# MINI_SAM_D51_014.net
KiCad netlist of a schematic drawn in EAGLE
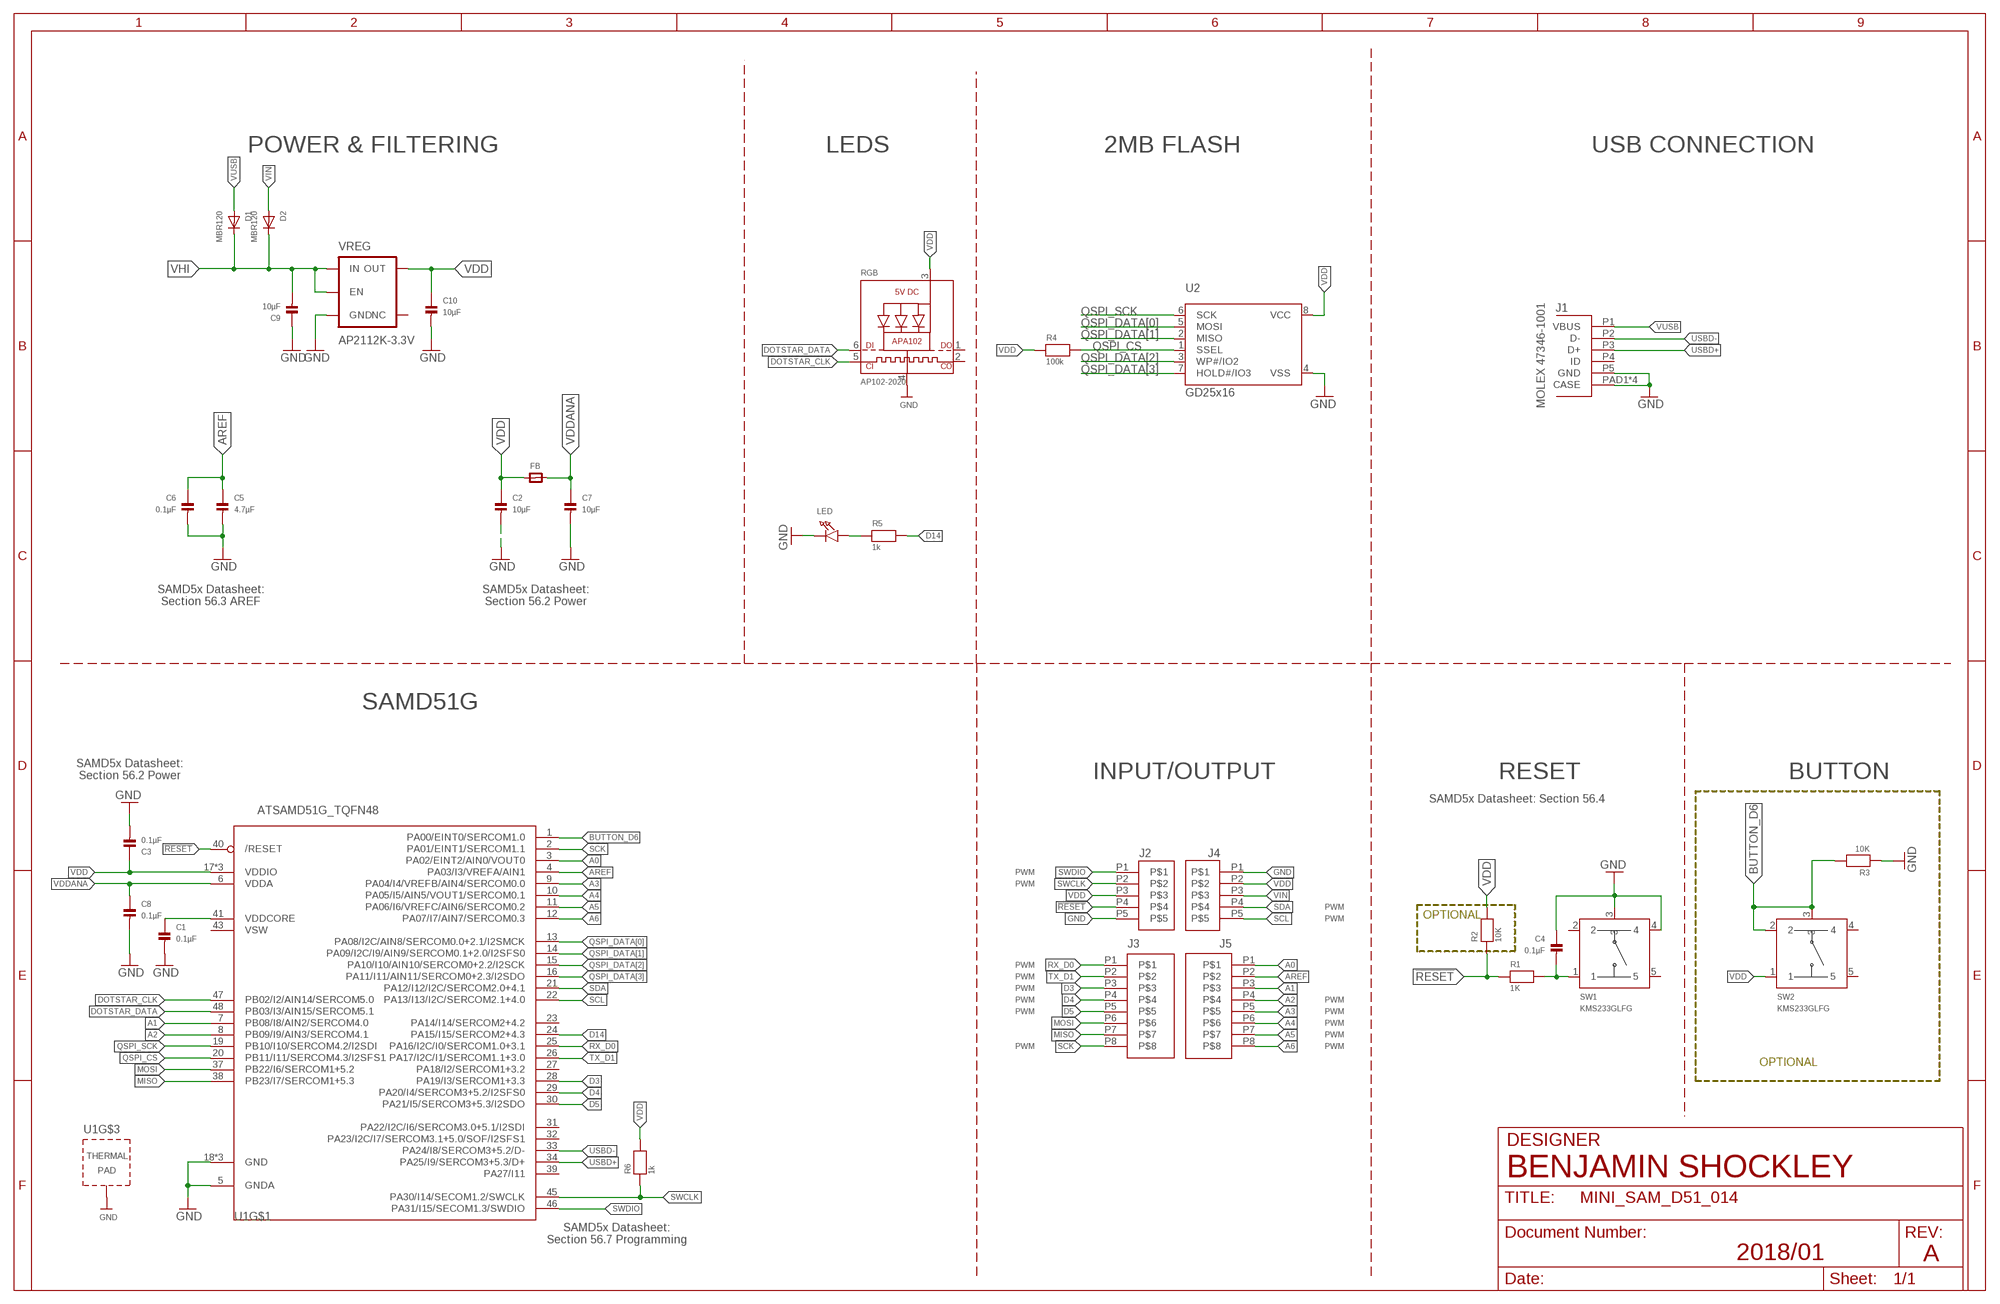
[diagram p0: schematic, sheet 1]

(export (version "E")
  (design (tool "Eeschema 10.0.6"))
  (components
    (comp (ref "C1")
      (value "0.1µF")
      (footprint "eagle-import:_0603MP")
      (libsource (lib "eagle-import") (part "CAP_CERAMIC_0603MP"))
    )
    (comp (ref "C2")
      (value "10µF")
      (footprint "eagle-import:_0603MP")
      (libsource (lib "eagle-import") (part "CAP_CERAMIC_0603MP"))
    )
    (comp (ref "C3")
      (value "0.1µF")
      (footprint "eagle-import:_0603MP")
      (libsource (lib "eagle-import") (part "CAP_CERAMIC_0603MP"))
    )
    (comp (ref "C4")
      (value "0.1µF")
      (footprint "eagle-import:_0603MP")
      (libsource (lib "eagle-import") (part "CAP_CERAMIC_0603MP"))
    )
    (comp (ref "C5")
      (value "4.7µF")
      (footprint "eagle-import:_0603MP")
      (libsource (lib "eagle-import") (part "CAP_CERAMIC_0603MP"))
    )
    (comp (ref "C6")
      (value "0.1µF")
      (footprint "eagle-import:_0603MP")
      (libsource (lib "eagle-import") (part "CAP_CERAMIC_0603MP"))
    )
    (comp (ref "C7")
      (value "10µF")
      (footprint "eagle-import:_0603MP")
      (libsource (lib "eagle-import") (part "CAP_CERAMIC_0603MP"))
    )
    (comp (ref "C8")
      (value "0.1µF")
      (footprint "eagle-import:_0603MP")
      (libsource (lib "eagle-import") (part "CAP_CERAMIC_0603MP"))
    )
    (comp (ref "C9")
      (value "10µF")
      (footprint "eagle-import:_0603MP")
      (libsource (lib "eagle-import") (part "CAP_CERAMIC_0603MP"))
    )
    (comp (ref "C10")
      (value "10µF")
      (footprint "eagle-import:_0603MP")
      (libsource (lib "eagle-import") (part "CAP_CERAMIC_0603MP"))
    )
    (comp (ref "D1")
      (value "MBR120")
      (footprint "eagle-import:SOD-123FL")
      (libsource (lib "eagle-import") (part "DIODE_SOD-123FL"))
    )
    (comp (ref "D2")
      (value "MBR120")
      (footprint "eagle-import:SOD-123FL")
      (libsource (lib "eagle-import") (part "DIODE_SOD-123FL"))
    )
    (comp (ref "FB")
      (value "FERRITE_0603MP")
      (footprint "eagle-import:_0603MP")
      (libsource (lib "eagle-import") (part "FERRITE_0603MP"))
    )
    (comp (ref "J1")
      (value "MOLEX_47346-100147346")
      (footprint "eagle-import:MOLEX_47346-1001")
      (libsource (lib "eagle-import") (part "MOLEX_47346-100147346"))
    )
    (comp (ref "J2")
      (value "1X5_HEADER_1.27MMCAST")
      (footprint "eagle-import:1X5_HEADER_1.27MM_CASTELLATED")
      (libsource (lib "eagle-import") (part "1X5_HEADER_1.27MMCAST"))
    )
    (comp (ref "J3")
      (value "1X8_HEADER_1.27MMCAST")
      (footprint "eagle-import:1X8_HEADER_1.27MM_CASTELLATED")
      (libsource (lib "eagle-import") (part "1X8_HEADER_1.27MMCAST"))
    )
    (comp (ref "J4")
      (value "1X5_HEADER_1.27MMCAST")
      (footprint "eagle-import:1X5_HEADER_1.27MM_CASTELLATED")
      (libsource (lib "eagle-import") (part "1X5_HEADER_1.27MMCAST"))
    )
    (comp (ref "J5")
      (value "1X8_HEADER_1.27MMCAST")
      (footprint "eagle-import:1X8_HEADER_1.27MM_CASTELLATED")
      (libsource (lib "eagle-import") (part "1X8_HEADER_1.27MMCAST"))
    )
    (comp (ref "LED")
      (value "LED0805_NOOUTLINE")
      (footprint "eagle-import:CHIPLED_0805_NOOUTLINE")
      (libsource (lib "eagle-import") (part "LED0805_NOOUTLINE"))
    )
    (comp (ref "R1")
      (value "1K")
      (footprint "eagle-import:_0603MP")
      (libsource (lib "eagle-import") (part "RESISTOR_0603MP"))
    )
    (comp (ref "R2")
      (value "10K")
      (footprint "eagle-import:_0603MP")
      (libsource (lib "eagle-import") (part "RESISTOR_0603MP"))
    )
    (comp (ref "R3")
      (value "10K")
      (footprint "eagle-import:_0603MP")
      (libsource (lib "eagle-import") (part "RESISTOR_0603MP"))
    )
    (comp (ref "R4")
      (value "100k")
      (footprint "eagle-import:_0603MP")
      (libsource (lib "eagle-import") (part "RESISTOR_0603MP"))
    )
    (comp (ref "R5")
      (value "1k")
      (footprint "eagle-import:_0603MP")
      (libsource (lib "eagle-import") (part "RESISTOR_0603MP"))
    )
    (comp (ref "R6")
      (value "1k")
      (footprint "eagle-import:_0603MP")
      (libsource (lib "eagle-import") (part "RESISTOR_0603MP"))
    )
    (comp (ref "RGB")
      (value "AP102-2020")
      (footprint "eagle-import:APA102_2020")
      (libsource (lib "eagle-import") (part "APA1022020"))
    )
    (comp (ref "SW1")
      (value "KMS233GLFG")
      (footprint "eagle-import:KMS_SWITCH")
      (libsource (lib "eagle-import") (part "KMS_SWITCHKMS"))
    )
    (comp (ref "SW2")
      (value "KMS233GLFG")
      (footprint "eagle-import:KMS_SWITCH")
      (libsource (lib "eagle-import") (part "KMS_SWITCHKMS"))
    )
    (comp (ref "U1")
      (value "ATSAMD51G_TQFN48")
      (footprint "eagle-import:TQFN48_7MM")
      (libsource (lib "eagle-import") (part "ATSAMD51G_TQFN48"))
    )
    (comp (ref "U2")
      (value "GD25x16")
      (footprint "eagle-import:USON8")
      (libsource (lib "eagle-import") (part "SPIFLASH_8PINUX"))
    )
    (comp (ref "VREG")
      (value "AP2112K-3.3V")
      (footprint "eagle-import:SOT23-5")
      (libsource (lib "eagle-import") (part "V_REG_AP2112K-3.3V"))
    )
  )
  (nets
    (net (code "1") (name "/VSW") (class "Default")
      (node (ref "U1") (pin "43") (pinfunction "VSW_43") (pintype "power_in"))
    )
    (net (code "2") (name "/~{RESET}") (class "Default")
      (node (ref "J2") (pin "P4") (pinfunction "P$4_P4") (pintype "bidirectional"))
      (node (ref "R1") (pin "1") (pinfunction "1_1") (pintype "passive"))
      (node (ref "R2") (pin "1") (pinfunction "1_1") (pintype "passive"))
      (node (ref "U1") (pin "40") (pinfunction "/RESET_40") (pintype "bidirectional"))
    )
    (net (code "3") (name "A0") (class "Default")
      (node (ref "J5") (pin "P1") (pinfunction "P$1_P1") (pintype "bidirectional"))
      (node (ref "U1") (pin "3") (pinfunction "PA02/EINT2/AIN0/VOUT0_3") (pintype "bidirectional"))
    )
    (net (code "4") (name "A1") (class "Default")
      (node (ref "J5") (pin "P3") (pinfunction "P$3_P3") (pintype "bidirectional"))
      (node (ref "U1") (pin "7") (pinfunction "PB08/I8/AIN2/SERCOM4.0_7") (pintype "bidirectional"))
    )
    (net (code "5") (name "A2") (class "Default")
      (node (ref "J5") (pin "P4") (pinfunction "P$4_P4") (pintype "bidirectional"))
      (node (ref "U1") (pin "8") (pinfunction "PB09/I9/AIN3/SERCOM4.1_8") (pintype "bidirectional"))
    )
    (net (code "6") (name "A3") (class "Default")
      (node (ref "J5") (pin "P5") (pinfunction "P$5_P5") (pintype "bidirectional"))
      (node (ref "U1") (pin "9") (pinfunction "PA04/I4/VREFB/AIN4/SERCOM0.0_9") (pintype "bidirectional"))
    )
    (net (code "7") (name "A4") (class "Default")
      (node (ref "J5") (pin "P6") (pinfunction "P$6_P6") (pintype "bidirectional"))
      (node (ref "U1") (pin "10") (pinfunction "PA05/I5/AIN5/VOUT1/SERCOM0.1_10") (pintype "bidirectional"))
    )
    (net (code "8") (name "A5") (class "Default")
      (node (ref "J5") (pin "P7") (pinfunction "P$7_P7") (pintype "bidirectional"))
      (node (ref "U1") (pin "11") (pinfunction "PA06/I6/VREFC/AIN6/SERCOM0.2_11") (pintype "bidirectional"))
    )
    (net (code "9") (name "A6") (class "Default")
      (node (ref "J5") (pin "P8") (pinfunction "P$8_P8") (pintype "bidirectional"))
      (node (ref "U1") (pin "12") (pinfunction "PA07/I7/AIN7/SERCOM0.3_12") (pintype "bidirectional"))
    )
    (net (code "10") (name "AREF") (class "Default")
      (node (ref "C5") (pin "1") (pinfunction "P$1_1") (pintype "passive"))
      (node (ref "C6") (pin "1") (pinfunction "P$1_1") (pintype "passive"))
      (node (ref "J5") (pin "P2") (pinfunction "P$2_P2") (pintype "bidirectional"))
      (node (ref "U1") (pin "4") (pinfunction "PA03/I3/VREFA/AIN1_4") (pintype "bidirectional"))
    )
    (net (code "11") (name "BUTTON_D6") (class "Default")
      (node (ref "R3") (pin "2") (pinfunction "2_2") (pintype "passive"))
      (node (ref "SW2") (pin "2") (pinfunction "2_2") (pintype "bidirectional"))
      (node (ref "SW2") (pin "3") (pinfunction "3_3") (pintype "bidirectional"))
      (node (ref "U1") (pin "1") (pinfunction "PA00/EINT0/SERCOM1.0_1") (pintype "bidirectional"))
    )
    (net (code "12") (name "D3") (class "Default")
      (node (ref "J3") (pin "P3") (pinfunction "P$3_P3") (pintype "bidirectional"))
      (node (ref "U1") (pin "28") (pinfunction "PA19/I3/SERCOM1+3.3_28") (pintype "bidirectional"))
    )
    (net (code "13") (name "D4") (class "Default")
      (node (ref "J3") (pin "P4") (pinfunction "P$4_P4") (pintype "bidirectional"))
      (node (ref "U1") (pin "29") (pinfunction "PA20/I4/SERCOM3+5.2/I2SFS0_29") (pintype "bidirectional"))
    )
    (net (code "14") (name "D5") (class "Default")
      (node (ref "J3") (pin "P5") (pinfunction "P$5_P5") (pintype "bidirectional"))
      (node (ref "U1") (pin "30") (pinfunction "PA21/I5/SERCOM3+5.3/I2SDO_30") (pintype "bidirectional"))
    )
    (net (code "15") (name "D14") (class "Default")
      (node (ref "R5") (pin "2") (pinfunction "2_2") (pintype "passive"))
      (node (ref "U1") (pin "24") (pinfunction "PA15/I15/SERCOM2+4.3_24") (pintype "bidirectional"))
    )
    (net (code "16") (name "DOTSTAR_CLK") (class "Default")
      (node (ref "RGB") (pin "5") (pinfunction "CKI_5") (pintype "input"))
      (node (ref "U1") (pin "47") (pinfunction "PB02/I2/AIN14/SERCOM5.0_47") (pintype "bidirectional"))
    )
    (net (code "17") (name "DOTSTAR_DATA") (class "Default")
      (node (ref "RGB") (pin "6") (pinfunction "DI_6") (pintype "input"))
      (node (ref "U1") (pin "48") (pinfunction "PB03/I3/AIN15/SERCOM5.1_48") (pintype "bidirectional"))
    )
    (net (code "18") (name "GND") (class "Default")
      (node (ref "C1") (pin "2") (pinfunction "P$2_2") (pintype "passive"))
      (node (ref "C10") (pin "2") (pinfunction "P$2_2") (pintype "passive"))
      (node (ref "C2") (pin "2") (pinfunction "P$2_2") (pintype "passive"))
      (node (ref "C3") (pin "2") (pinfunction "P$2_2") (pintype "passive"))
      (node (ref "C4") (pin "1") (pinfunction "P$1_1") (pintype "passive"))
      (node (ref "C5") (pin "2") (pinfunction "P$2_2") (pintype "passive"))
      (node (ref "C6") (pin "2") (pinfunction "P$2_2") (pintype "passive"))
      (node (ref "C7") (pin "2") (pinfunction "P$2_2") (pintype "passive"))
      (node (ref "C8") (pin "2") (pinfunction "P$2_2") (pintype "passive"))
      (node (ref "C9") (pin "1") (pinfunction "P$1_1") (pintype "passive"))
      (node (ref "J1") (pin "P5") (pinfunction "GND_P5") (pintype "power_in"))
      (node (ref "J1") (pin "PAD1") (pinfunction "CASE_PAD1") (pintype "bidirectional"))
      (node (ref "J1") (pin "PAD2") (pinfunction "CASE_PAD2") (pintype "bidirectional"))
      (node (ref "J1") (pin "PAD3") (pinfunction "CASE_PAD3") (pintype "bidirectional"))
      (node (ref "J1") (pin "PAD4") (pinfunction "CASE_PAD4") (pintype "bidirectional"))
      (node (ref "J2") (pin "P5") (pinfunction "P$5_P5") (pintype "bidirectional"))
      (node (ref "J4") (pin "P1") (pinfunction "P$1_P1") (pintype "bidirectional"))
      (node (ref "LED") (pin "C") (pinfunction "C_C") (pintype "passive"))
      (node (ref "R3") (pin "1") (pinfunction "1_1") (pintype "passive"))
      (node (ref "RGB") (pin "4") (pinfunction "GND_4") (pintype "power_in"))
      (node (ref "SW1") (pin "3") (pinfunction "3_3") (pintype "bidirectional"))
      (node (ref "SW1") (pin "4") (pinfunction "4_4") (pintype "bidirectional"))
      (node (ref "U1") (pin "18") (pinfunction "GND_18") (pintype "power_in"))
      (node (ref "U1") (pin "35") (pinfunction "GND_35") (pintype "power_in"))
      (node (ref "U1") (pin "42") (pinfunction "GND_42") (pintype "power_in"))
      (node (ref "U1") (pin "5") (pinfunction "GNDA_5") (pintype "power_in"))
      (node (ref "U1") (pin "THERMAL") (pinfunction "TP_THERMAL") (pintype "power_in"))
      (node (ref "U2") (pin "4") (pinfunction "VSS_4") (pintype "bidirectional"))
      (node (ref "VREG") (pin "2") (pinfunction "GND_2") (pintype "input"))
    )
    (net (code "19") (name "MISO") (class "Default")
      (node (ref "J3") (pin "P7") (pinfunction "P$7_P7") (pintype "bidirectional"))
      (node (ref "U1") (pin "38") (pinfunction "PB23/I7/SERCOM1+5.3_38") (pintype "bidirectional"))
    )
    (net (code "20") (name "MOSI") (class "Default")
      (node (ref "J3") (pin "P6") (pinfunction "P$6_P6") (pintype "bidirectional"))
      (node (ref "U1") (pin "37") (pinfunction "PB22/I6/SERCOM1+5.2_37") (pintype "bidirectional"))
    )
    (net (code "21") (name "Net-(C1-P$1)") (class "Default")
      (node (ref "C1") (pin "1") (pinfunction "P$1_1") (pintype "passive"))
      (node (ref "U1") (pin "41") (pinfunction "VDDCORE_41") (pintype "power_in"))
    )
    (net (code "22") (name "Net-(C4-P$2)") (class "Default")
      (node (ref "C4") (pin "2") (pinfunction "P$2_2") (pintype "passive"))
      (node (ref "R1") (pin "2") (pinfunction "2_2") (pintype "passive"))
      (node (ref "SW1") (pin "1") (pinfunction "1_1") (pintype "bidirectional"))
    )
    (net (code "23") (name "Net-(LED-PadA)") (class "Default")
      (node (ref "LED") (pin "A") (pinfunction "A_A") (pintype "passive"))
      (node (ref "R5") (pin "1") (pinfunction "1_1") (pintype "passive"))
    )
    (net (code "24") (name "QSPI_CS") (class "Default")
      (node (ref "R4") (pin "2") (pinfunction "2_2") (pintype "passive"))
      (node (ref "U1") (pin "20") (pinfunction "PB11/I11/SERCOM4.3/I2SFS1_20") (pintype "bidirectional"))
      (node (ref "U2") (pin "1") (pinfunction "SSEL_1") (pintype "bidirectional"))
    )
    (net (code "25") (name "QSPI_DATA[0]") (class "Default")
      (node (ref "U1") (pin "13") (pinfunction "PA08/I2C/AIN8/SERCOM0.0+2.1/I2SMCK_13") (pintype "bidirectional"))
      (node (ref "U2") (pin "5") (pinfunction "MOSI_5") (pintype "bidirectional"))
    )
    (net (code "26") (name "QSPI_DATA[1]") (class "Default")
      (node (ref "U1") (pin "14") (pinfunction "PA09/I2C/I9/AIN9/SERCOM0.1+2.0/I2SFS0_14") (pintype "bidirectional"))
      (node (ref "U2") (pin "2") (pinfunction "MISO_2") (pintype "bidirectional"))
    )
    (net (code "27") (name "QSPI_DATA[2]") (class "Default")
      (node (ref "U1") (pin "15") (pinfunction "PA10/I10/AIN10/SERCOM0+2.2/I2SCK_15") (pintype "bidirectional"))
      (node (ref "U2") (pin "3") (pinfunction "WP#/IO2_3") (pintype "bidirectional"))
    )
    (net (code "28") (name "QSPI_DATA[3]") (class "Default")
      (node (ref "U1") (pin "16") (pinfunction "PA11/I11/AIN11/SERCOM0+2.3/I2SDO_16") (pintype "bidirectional"))
      (node (ref "U2") (pin "7") (pinfunction "HOLD#/IO3_7") (pintype "bidirectional"))
    )
    (net (code "29") (name "QSPI_SCK") (class "Default")
      (node (ref "U1") (pin "19") (pinfunction "PB10/I10/SERCOM4.2/I2SDI_19") (pintype "bidirectional"))
      (node (ref "U2") (pin "6") (pinfunction "SCK_6") (pintype "bidirectional"))
    )
    (net (code "30") (name "RX_D0") (class "Default")
      (node (ref "J3") (pin "P1") (pinfunction "P$1_P1") (pintype "bidirectional"))
      (node (ref "U1") (pin "25") (pinfunction "PA16/I2C/I0/SERCOM1.0+3.1_25") (pintype "bidirectional"))
    )
    (net (code "31") (name "SCK") (class "Default")
      (node (ref "J3") (pin "P8") (pinfunction "P$8_P8") (pintype "bidirectional"))
      (node (ref "U1") (pin "2") (pinfunction "PA01/EINT1/SERCOM1.1_2") (pintype "bidirectional"))
    )
    (net (code "32") (name "SCL") (class "Default")
      (node (ref "J4") (pin "P5") (pinfunction "P$5_P5") (pintype "bidirectional"))
      (node (ref "U1") (pin "22") (pinfunction "PA13/I13/I2C/SERCOM2.1+4.0_22") (pintype "bidirectional"))
    )
    (net (code "33") (name "SDA") (class "Default")
      (node (ref "J4") (pin "P4") (pinfunction "P$4_P4") (pintype "bidirectional"))
      (node (ref "U1") (pin "21") (pinfunction "PA12/I12/I2C/SERCOM2.0+4.1_21") (pintype "bidirectional"))
    )
    (net (code "34") (name "SWCLK") (class "Default")
      (node (ref "J2") (pin "P2") (pinfunction "P$2_P2") (pintype "bidirectional"))
      (node (ref "R6") (pin "1") (pinfunction "1_1") (pintype "passive"))
      (node (ref "U1") (pin "45") (pinfunction "PA30/I14/SECOM1.2/SWCLK_45") (pintype "bidirectional"))
    )
    (net (code "35") (name "SWDIO") (class "Default")
      (node (ref "J2") (pin "P1") (pinfunction "P$1_P1") (pintype "bidirectional"))
      (node (ref "U1") (pin "46") (pinfunction "PA31/I15/SECOM1.3/SWDIO_46") (pintype "bidirectional"))
    )
    (net (code "36") (name "TX_D1") (class "Default")
      (node (ref "J3") (pin "P2") (pinfunction "P$2_P2") (pintype "bidirectional"))
      (node (ref "U1") (pin "26") (pinfunction "PA17/I2C/I1/SERCOM1.1+3.0_26") (pintype "bidirectional"))
    )
    (net (code "37") (name "USBD+") (class "Default")
      (node (ref "J1") (pin "P3") (pinfunction "D+_P3") (pintype "bidirectional"))
      (node (ref "U1") (pin "34") (pinfunction "PA25/I9/SERCOM3+5.3/D+_34") (pintype "bidirectional"))
    )
    (net (code "38") (name "USBD-") (class "Default")
      (node (ref "J1") (pin "P2") (pinfunction "D-_P2") (pintype "bidirectional"))
      (node (ref "U1") (pin "33") (pinfunction "PA24/I8/SERCOM3+5.2/D-_33") (pintype "bidirectional"))
    )
    (net (code "39") (name "VDD") (class "Default")
      (node (ref "C10") (pin "1") (pinfunction "P$1_1") (pintype "passive"))
      (node (ref "C2") (pin "1") (pinfunction "P$1_1") (pintype "passive"))
      (node (ref "C3") (pin "1") (pinfunction "P$1_1") (pintype "passive"))
      (node (ref "FB") (pin "1") (pinfunction "P$1_1") (pintype "passive"))
      (node (ref "J2") (pin "P3") (pinfunction "P$3_P3") (pintype "bidirectional"))
      (node (ref "J4") (pin "P2") (pinfunction "P$2_P2") (pintype "bidirectional"))
      (node (ref "R2") (pin "2") (pinfunction "2_2") (pintype "passive"))
      (node (ref "R4") (pin "1") (pinfunction "1_1") (pintype "passive"))
      (node (ref "R6") (pin "2") (pinfunction "2_2") (pintype "passive"))
      (node (ref "RGB") (pin "3") (pinfunction "VDD_3") (pintype "power_in"))
      (node (ref "SW2") (pin "1") (pinfunction "1_1") (pintype "bidirectional"))
      (node (ref "U1") (pin "17") (pinfunction "VDDIO_17") (pintype "power_in"))
      (node (ref "U1") (pin "36") (pinfunction "VDDIO_36") (pintype "power_in"))
      (node (ref "U1") (pin "44") (pinfunction "VDDIO_44") (pintype "power_in"))
      (node (ref "U2") (pin "8") (pinfunction "VCC_8") (pintype "bidirectional"))
      (node (ref "VREG") (pin "5") (pinfunction "OUT_5") (pintype "passive"))
    )
    (net (code "40") (name "VDDANA") (class "Default")
      (node (ref "C7") (pin "1") (pinfunction "P$1_1") (pintype "passive"))
      (node (ref "C8") (pin "1") (pinfunction "P$1_1") (pintype "passive"))
      (node (ref "FB") (pin "2") (pinfunction "P$2_2") (pintype "passive"))
      (node (ref "U1") (pin "6") (pinfunction "VDDA_6") (pintype "power_in"))
    )
    (net (code "41") (name "VHI") (class "Default")
      (node (ref "C9") (pin "2") (pinfunction "P$2_2") (pintype "passive"))
      (node (ref "D1") (pin "C") (pinfunction "C_C") (pintype "passive"))
      (node (ref "D2") (pin "C") (pinfunction "C_C") (pintype "passive"))
      (node (ref "VREG") (pin "1") (pinfunction "IN_1") (pintype "input"))
      (node (ref "VREG") (pin "3") (pinfunction "EN_3") (pintype "input"))
    )
    (net (code "42") (name "VIN") (class "Default")
      (node (ref "D2") (pin "A") (pinfunction "A_A") (pintype "passive"))
      (node (ref "J4") (pin "P3") (pinfunction "P$3_P3") (pintype "bidirectional"))
    )
    (net (code "43") (name "VUSB") (class "Default")
      (node (ref "D1") (pin "A") (pinfunction "A_A") (pintype "passive"))
      (node (ref "J1") (pin "P1") (pinfunction "VBUS_P1") (pintype "power_in"))
    )
    (net (code "44") (name "unconnected-(J1-ID-PadP4)") (class "Default")
      (node (ref "J1") (pin "P4") (pinfunction "ID_P4") (pintype "bidirectional"))
    )
    (net (code "45") (name "unconnected-(RGB-CKO-Pad2)") (class "Default")
      (node (ref "RGB") (pin "2") (pinfunction "CKO_2") (pintype "output"))
    )
    (net (code "46") (name "unconnected-(RGB-DO-Pad1)") (class "Default")
      (node (ref "RGB") (pin "1") (pinfunction "DO_1") (pintype "output"))
    )
    (net (code "47") (name "unconnected-(SW1-Pad2)") (class "Default")
      (node (ref "SW1") (pin "2") (pinfunction "2_2") (pintype "bidirectional"))
    )
    (net (code "48") (name "unconnected-(SW1-Pad5)") (class "Default")
      (node (ref "SW1") (pin "5") (pinfunction "5_5") (pintype "bidirectional"))
    )
    (net (code "49") (name "unconnected-(SW2-Pad4)") (class "Default")
      (node (ref "SW2") (pin "4") (pinfunction "4_4") (pintype "bidirectional"))
    )
    (net (code "50") (name "unconnected-(SW2-Pad5)") (class "Default")
      (node (ref "SW2") (pin "5") (pinfunction "5_5") (pintype "bidirectional"))
    )
    (net (code "51") (name "unconnected-(U1A-PA14{slash}I14{slash}SERCOM2+4.2-Pad23)") (class "Default")
      (node (ref "U1") (pin "23") (pinfunction "PA14/I14/SERCOM2+4.2_23") (pintype "bidirectional"))
    )
    (net (code "52") (name "unconnected-(U1A-PA18{slash}I2{slash}SERCOM1+3.2-Pad27)") (class "Default")
      (node (ref "U1") (pin "27") (pinfunction "PA18/I2/SERCOM1+3.2_27") (pintype "bidirectional"))
    )
    (net (code "53") (name "unconnected-(U1A-PA22{slash}I2C{slash}I6{slash}SERCOM3.0+5.1{slash}I2SDI-Pad31)") (class "Default")
      (node (ref "U1") (pin "31") (pinfunction "PA22/I2C/I6/SERCOM3.0+5.1/I2SDI_31") (pintype "bidirectional"))
    )
    (net (code "54") (name "unconnected-(U1A-PA23{slash}I2C{slash}I7{slash}SERCOM3.1+5.0{slash}SOF{slash}I2SFS1-Pad32)") (class "Default")
      (node (ref "U1") (pin "32") (pinfunction "PA23/I2C/I7/SERCOM3.1+5.0/SOF/I2SFS1_32") (pintype "bidirectional"))
    )
    (net (code "55") (name "unconnected-(U1A-PA27{slash}I11-Pad39)") (class "Default")
      (node (ref "U1") (pin "39") (pinfunction "PA27/I11_39") (pintype "bidirectional"))
    )
    (net (code "56") (name "unconnected-(VREG-NC-Pad4)") (class "Default")
      (node (ref "VREG") (pin "4") (pinfunction "NC_4") (pintype "input"))
    )
  )
)
